# Pixie84.net
KiCad netlist of a schematic drawn in EAGLE
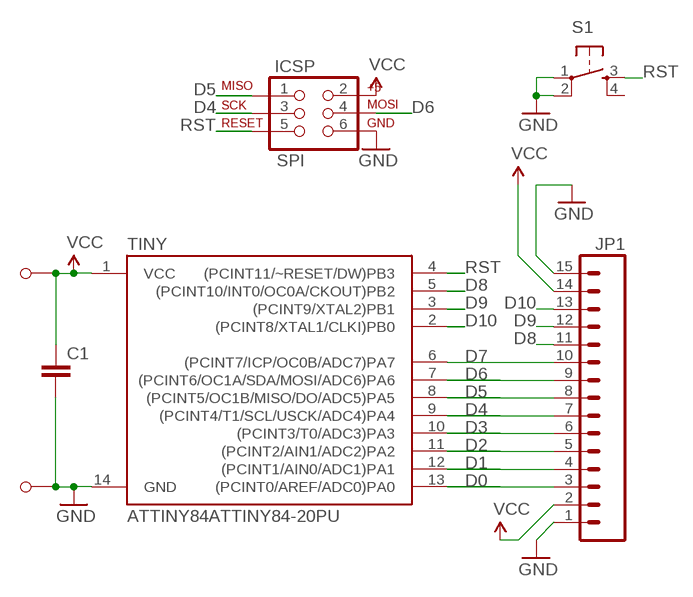
[diagram p0: schematic, sheet 1]

(export (version "E")
  (design (tool "Eeschema 10.0.6"))
  (components
    (comp (ref "C1")
      (value "CAPPTH")
      (footprint "eagle-import:CAP-PTH-SMALL")
      (libsource (lib "eagle-import") (part "CAPPTH"))
    )
    (comp (ref "ICSP")
      (value "SPI")
      (footprint "eagle-import:2X3-NS")
      (libsource (lib "eagle-import") (part "AVR_SPI_PRG_6LABELED"))
    )
    (comp (ref "JP1")
      (value "M15")
      (footprint "eagle-import:1X15")
      (libsource (lib "eagle-import") (part "M15"))
    )
    (comp (ref "S1")
      (value "TAC_SWITCHPTH")
      (footprint "eagle-import:TACTILE-PTH")
      (libsource (lib "eagle-import") (part "TAC_SWITCHPTH"))
    )
    (comp (ref "TINY")
      (value "ATTINY84ATTINY84-20PU")
      (footprint "eagle-import:DIL14")
      (libsource (lib "eagle-import") (part "ATTINY84ATTINY84-20PU"))
    )
    (comp (ref "U$1")
      (value "M1")
      (footprint "eagle-import:M1_NO_STRAIN")
      (libsource (lib "eagle-import") (part "M1"))
    )
    (comp (ref "U$2")
      (value "M1")
      (footprint "eagle-import:M1_NO_STRAIN")
      (libsource (lib "eagle-import") (part "M1"))
    )
  )
  (nets
    (net (code "1") (name "/D0") (class "Default")
      (node (ref "JP1") (pin "3") (pinfunction "3_3") (pintype "passive"))
      (node (ref "TINY") (pin "13") (pinfunction "(PCINT0/AREF/ADC0)PA0_13") (pintype "bidirectional"))
    )
    (net (code "2") (name "/D1") (class "Default")
      (node (ref "JP1") (pin "4") (pinfunction "4_4") (pintype "passive"))
      (node (ref "TINY") (pin "12") (pinfunction "(PCINT1/AIN0/ADC1)PA1_12") (pintype "bidirectional"))
    )
    (net (code "3") (name "/D2") (class "Default")
      (node (ref "JP1") (pin "5") (pinfunction "5_5") (pintype "passive"))
      (node (ref "TINY") (pin "11") (pinfunction "(PCINT2/AIN1/ADC2)PA2_11") (pintype "bidirectional"))
    )
    (net (code "4") (name "/D3") (class "Default")
      (node (ref "JP1") (pin "6") (pinfunction "6_6") (pintype "passive"))
      (node (ref "TINY") (pin "10") (pinfunction "(PCINT3/T0/ADC3)PA3_10") (pintype "bidirectional"))
    )
    (net (code "5") (name "/D4") (class "Default")
      (node (ref "ICSP") (pin "3") (pinfunction "SCK_3") (pintype "passive"))
      (node (ref "JP1") (pin "7") (pinfunction "7_7") (pintype "passive"))
      (node (ref "TINY") (pin "9") (pinfunction "(PCINT4/T1/SCL/USCK/ADC4)PA4_9") (pintype "bidirectional"))
    )
    (net (code "6") (name "/D5") (class "Default")
      (node (ref "ICSP") (pin "1") (pinfunction "MISO_1") (pintype "passive"))
      (node (ref "JP1") (pin "8") (pinfunction "8_8") (pintype "passive"))
      (node (ref "TINY") (pin "8") (pinfunction "(PCINT5/OC1B/MISO/DO/ADC5)PA5_8") (pintype "bidirectional"))
    )
    (net (code "7") (name "/D6") (class "Default")
      (node (ref "ICSP") (pin "4") (pinfunction "MOSI_4") (pintype "passive"))
      (node (ref "JP1") (pin "9") (pinfunction "9_9") (pintype "passive"))
      (node (ref "TINY") (pin "7") (pinfunction "(PCINT6/OC1A/SDA/MOSI/ADC6)PA6_7") (pintype "bidirectional"))
    )
    (net (code "8") (name "/D7") (class "Default")
      (node (ref "JP1") (pin "10") (pinfunction "10_10") (pintype "passive"))
      (node (ref "TINY") (pin "6") (pinfunction "(PCINT7/ICP/OC0B/ADC7)PA7_6") (pintype "bidirectional"))
    )
    (net (code "9") (name "/D8") (class "Default")
      (node (ref "JP1") (pin "11") (pinfunction "11_11") (pintype "passive"))
      (node (ref "TINY") (pin "5") (pinfunction "(PCINT10/INT0/OC0A/CKOUT)PB2_5") (pintype "bidirectional"))
    )
    (net (code "10") (name "/D9") (class "Default")
      (node (ref "JP1") (pin "12") (pinfunction "12_12") (pintype "passive"))
      (node (ref "TINY") (pin "3") (pinfunction "(PCINT9/XTAL2)PB1_3") (pintype "bidirectional"))
    )
    (net (code "11") (name "/D10") (class "Default")
      (node (ref "JP1") (pin "13") (pinfunction "13_13") (pintype "passive"))
      (node (ref "TINY") (pin "2") (pinfunction "(PCINT8/XTAL1/CLKI)PB0_2") (pintype "bidirectional"))
    )
    (net (code "12") (name "/RST") (class "Default")
      (node (ref "ICSP") (pin "5") (pinfunction "RST_5") (pintype "passive"))
      (node (ref "S1") (pin "3") (pinfunction "3_3") (pintype "passive"))
      (node (ref "TINY") (pin "4") (pinfunction "(PCINT11/~{RESET/DW})PB3_4") (pintype "bidirectional"))
    )
    (net (code "13") (name "GND") (class "Default")
      (node (ref "C1") (pin "2") (pinfunction "2_2") (pintype "passive"))
      (node (ref "ICSP") (pin "6") (pinfunction "GND_6") (pintype "passive"))
      (node (ref "JP1") (pin "1") (pinfunction "1_1") (pintype "passive"))
      (node (ref "JP1") (pin "15") (pinfunction "15_15") (pintype "passive"))
      (node (ref "S1") (pin "1") (pinfunction "1_1") (pintype "passive"))
      (node (ref "S1") (pin "2") (pinfunction "2_2") (pintype "passive"))
      (node (ref "TINY") (pin "14") (pinfunction "GND_14") (pintype "bidirectional"))
      (node (ref "U$2") (pin "P$1") (pinfunction "P$1_P$1") (pintype "bidirectional"))
    )
    (net (code "14") (name "VCC") (class "Default")
      (node (ref "C1") (pin "1") (pinfunction "1_1") (pintype "passive"))
      (node (ref "ICSP") (pin "2") (pinfunction "V+_2") (pintype "passive"))
      (node (ref "JP1") (pin "14") (pinfunction "14_14") (pintype "passive"))
      (node (ref "JP1") (pin "2") (pinfunction "2_2") (pintype "passive"))
      (node (ref "TINY") (pin "1") (pinfunction "VCC_1") (pintype "bidirectional"))
      (node (ref "U$1") (pin "P$1") (pinfunction "P$1_P$1") (pintype "bidirectional"))
    )
    (net (code "15") (name "unconnected-(S1-Pad4)") (class "Default")
      (node (ref "S1") (pin "4") (pinfunction "4_4") (pintype "passive"))
    )
  )
)
